# AC2DC.net
KiCad netlist of a schematic drawn in EAGLE
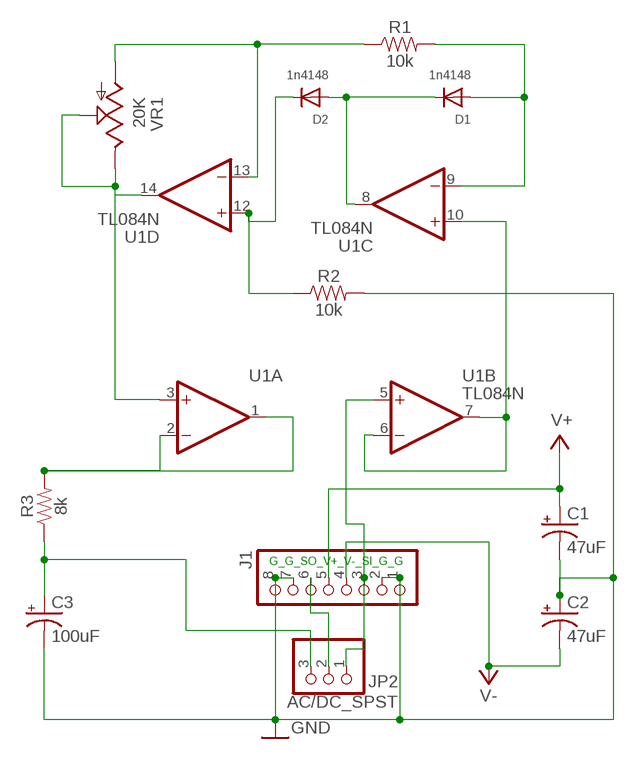
[diagram p0: schematic, sheet 1]

(export (version "E")
  (design (tool "Eeschema 10.0.6"))
  (components
    (comp (ref "AC/DC_SPST")
      (value "JP2")
      (footprint "eagle-import:1X03")
      (libsource (lib "eagle-import") (part "PINHD-1X3"))
    )
    (comp (ref "C1")
      (value "47uF")
      (footprint "eagle-import:E5-4")
      (libsource (lib "eagle-import") (part "CPOL-USE5-4"))
    )
    (comp (ref "C2")
      (value "47uF")
      (footprint "eagle-import:E5-4")
      (libsource (lib "eagle-import") (part "CPOL-USE5-4"))
    )
    (comp (ref "C3")
      (value "100uF")
      (footprint "eagle-import:E5-4")
      (libsource (lib "eagle-import") (part "CPOL-USE5-4"))
    )
    (comp (ref "D1")
      (value "1n4148")
      (footprint "eagle-import:DO-1N4148")
      (libsource (lib "eagle-import") (part "DIODEDO-1N4148"))
    )
    (comp (ref "D2")
      (value "1n4148")
      (footprint "eagle-import:DO-1N4148")
      (libsource (lib "eagle-import") (part "DIODEDO-1N4148"))
    )
    (comp (ref "G_G_SO_V+_V-_SI_G_G")
      (value "J1")
      (footprint "eagle-import:1X08-BIG")
      (libsource (lib "eagle-import") (part "PINHD-1X8BIG"))
    )
    (comp (ref "R1")
      (value "10k")
      (footprint "eagle-import:AXIAL-0.3")
      (libsource (lib "eagle-import") (part "10KOHM-HORIZ-1/4W-5%"))
    )
    (comp (ref "R2")
      (value "10k")
      (footprint "eagle-import:AXIAL-0.3")
      (libsource (lib "eagle-import") (part "10KOHM-HORIZ-1/4W-5%"))
    )
    (comp (ref "R3")
      (value "8k")
      (footprint "eagle-import:AXIAL-0.3")
      (libsource (lib "eagle-import") (part "10KOHM-HORIZ-1/4W-5%"))
    )
    (comp (ref "U1")
      (value "TL084N")
      (footprint "eagle-import:DIL14")
      (libsource (lib "eagle-import") (part "TL084N"))
    )
    (comp (ref "VR1")
      (value "20K")
      (footprint "eagle-import:S64W")
      (libsource (lib "eagle-import") (part "TRIM_US-S64W"))
    )
  )
  (nets
    (net (code "1") (name "GND") (class "Default")
      (node (ref "C1") (pin "-") (pinfunction "-_-") (pintype "passive"))
      (node (ref "C2") (pin "+") (pinfunction "+_+") (pintype "passive"))
      (node (ref "C3") (pin "-") (pinfunction "-_-") (pintype "passive"))
      (node (ref "G_G_SO_V+_V-_SI_G_G") (pin "1") (pinfunction "1_1") (pintype "passive"))
      (node (ref "G_G_SO_V+_V-_SI_G_G") (pin "2") (pinfunction "2_2") (pintype "passive"))
      (node (ref "G_G_SO_V+_V-_SI_G_G") (pin "7") (pinfunction "7_7") (pintype "passive"))
      (node (ref "G_G_SO_V+_V-_SI_G_G") (pin "8") (pinfunction "8_8") (pintype "passive"))
      (node (ref "R2") (pin "P$2") (pinfunction "2_P$2") (pintype "passive"))
    )
    (net (code "2") (name "Net-(AC/DC_SPST-Pad2)") (class "Default")
      (node (ref "AC/DC_SPST") (pin "2") (pinfunction "2_2") (pintype "passive"))
      (node (ref "G_G_SO_V+_V-_SI_G_G") (pin "6") (pinfunction "6_6") (pintype "passive"))
    )
    (net (code "3") (name "Net-(R1-1)") (class "Default")
      (node (ref "R1") (pin "P$1") (pinfunction "1_P$1") (pintype "passive"))
      (node (ref "U1") (pin "13") (pinfunction "-IN_13") (pintype "input"))
      (node (ref "VR1") (pin "A") (pinfunction "A_A") (pintype "passive"))
    )
    (net (code "4") (name "Net-(R1-2)") (class "Default")
      (node (ref "D1") (pin "A") (pinfunction "A_A") (pintype "passive"))
      (node (ref "R1") (pin "P$2") (pinfunction "2_P$2") (pintype "passive"))
      (node (ref "U1") (pin "9") (pinfunction "-IN_9") (pintype "input"))
    )
    (net (code "5") (name "Net-(R2-1)") (class "Default")
      (node (ref "D2") (pin "C") (pinfunction "C_C") (pintype "passive"))
      (node (ref "R2") (pin "P$1") (pinfunction "1_P$1") (pintype "passive"))
      (node (ref "U1") (pin "12") (pinfunction "+IN_12") (pintype "input"))
    )
    (net (code "6") (name "Net-(R3-1)") (class "Default")
      (node (ref "AC/DC_SPST") (pin "3") (pinfunction "3_3") (pintype "passive"))
      (node (ref "C3") (pin "+") (pinfunction "+_+") (pintype "passive"))
      (node (ref "R3") (pin "P$1") (pinfunction "1_P$1") (pintype "passive"))
    )
    (net (code "7") (name "Net-(R3-2)") (class "Default")
      (node (ref "R3") (pin "P$2") (pinfunction "2_P$2") (pintype "passive"))
      (node (ref "U1") (pin "1") (pinfunction "OUT_1") (pintype "output"))
      (node (ref "U1") (pin "2") (pinfunction "-IN_2") (pintype "input"))
    )
    (net (code "8") (name "Net-(U1A-+IN)") (class "Default")
      (node (ref "U1") (pin "14") (pinfunction "OUT_14") (pintype "output"))
      (node (ref "U1") (pin "3") (pinfunction "+IN_3") (pintype "input"))
      (node (ref "VR1") (pin "E") (pinfunction "E_E") (pintype "passive"))
      (node (ref "VR1") (pin "S") (pinfunction "S_S") (pintype "passive"))
    )
    (net (code "9") (name "Net-(U1B-+IN)") (class "Default")
      (node (ref "AC/DC_SPST") (pin "1") (pinfunction "1_1") (pintype "passive"))
      (node (ref "G_G_SO_V+_V-_SI_G_G") (pin "3") (pinfunction "3_3") (pintype "passive"))
      (node (ref "U1") (pin "5") (pinfunction "+IN_5") (pintype "input"))
    )
    (net (code "10") (name "Net-(U1B--IN)") (class "Default")
      (node (ref "U1") (pin "10") (pinfunction "+IN_10") (pintype "input"))
      (node (ref "U1") (pin "6") (pinfunction "-IN_6") (pintype "input"))
      (node (ref "U1") (pin "7") (pinfunction "OUT_7") (pintype "output"))
    )
    (net (code "11") (name "Net-(U1C-OUT)") (class "Default")
      (node (ref "D1") (pin "C") (pinfunction "C_C") (pintype "passive"))
      (node (ref "D2") (pin "A") (pinfunction "A_A") (pintype "passive"))
      (node (ref "U1") (pin "8") (pinfunction "OUT_8") (pintype "output"))
    )
    (net (code "12") (name "V+") (class "Default")
      (node (ref "C1") (pin "+") (pinfunction "+_+") (pintype "passive"))
      (node (ref "G_G_SO_V+_V-_SI_G_G") (pin "5") (pinfunction "5_5") (pintype "passive"))
    )
    (net (code "13") (name "V-") (class "Default")
      (node (ref "C2") (pin "-") (pinfunction "-_-") (pintype "passive"))
      (node (ref "G_G_SO_V+_V-_SI_G_G") (pin "4") (pinfunction "4_4") (pintype "passive"))
    )
  )
)
